# pir-tara.net
KiCad netlist of a schematic drawn in Altium Designer
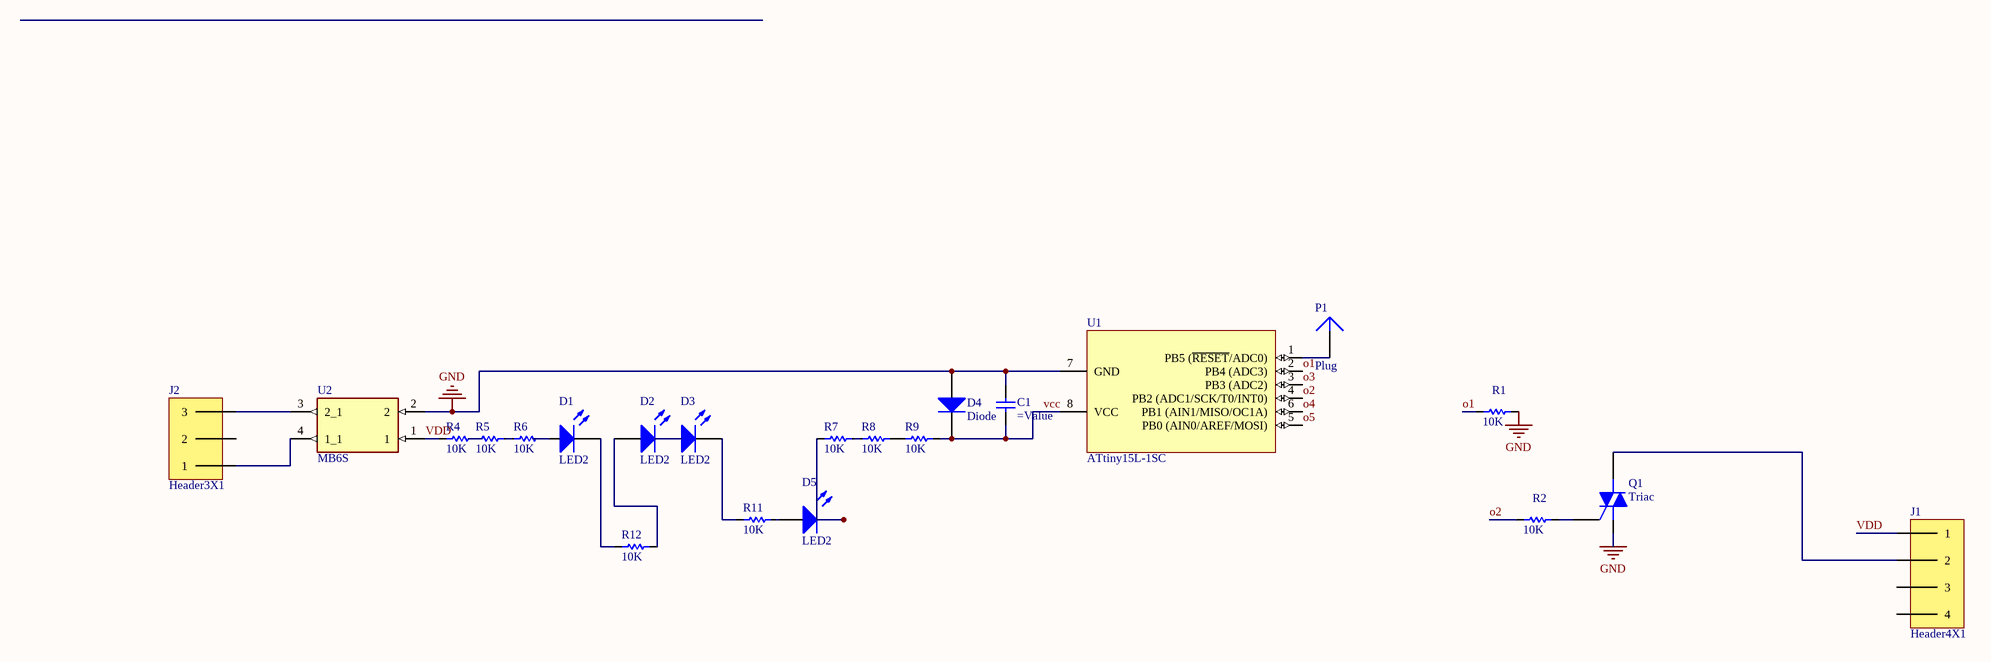
[diagram p0: pir-tara.SchDoc]

(export (version "E")
  (design (tool "Eeschema 10.0.6"))
  (components
    (comp (ref "C1")
      (value "~")
      (footprint "CAP 1206")
      (description "Capacitor")
      (libsource (lib "AltiumLib1") (part "Capacitor"))
    )
    (comp (ref "D1")
      (value "LED2")
      (footprint "3.2X1.6X1.1")
      (description "Typical RED, GREEN, YELLOW, AMBER GaAs LED")
      (fields (field (name "PUBLISHER") "Altium Limited"))
      (libsource (lib "Miscellaneous Devices") (part "LED2"))
    )
    (comp (ref "D2")
      (value "LED2")
      (footprint "3.2X1.6X1.1")
      (description "Typical RED, GREEN, YELLOW, AMBER GaAs LED")
      (fields (field (name "PUBLISHER") "Altium Limited"))
      (libsource (lib "Miscellaneous Devices") (part "LED2"))
    )
    (comp (ref "D3")
      (value "LED2")
      (footprint "3.2X1.6X1.1")
      (description "Typical RED, GREEN, YELLOW, AMBER GaAs LED")
      (fields (field (name "PUBLISHER") "Altium Limited"))
      (libsource (lib "Miscellaneous Devices") (part "LED2"))
    )
    (comp (ref "D4")
      (value "Diode")
      (footprint "C1206")
      (description "Default Diode")
      (fields (field (name "PUBLISHER") "Altium Limited"))
      (libsource (lib "Miscellaneous Devices") (part "Diode"))
    )
    (comp (ref "D5")
      (value "LED2")
      (footprint "3.2X1.6X1.1")
      (description "Typical RED, GREEN, YELLOW, AMBER GaAs LED")
      (fields (field (name "PUBLISHER") "Altium Limited"))
      (libsource (lib "Miscellaneous Devices") (part "LED2"))
    )
    (comp (ref "J1")
      (value "Header4X1")
      (footprint "HEADER 4X1")
      (libsource (lib "AltiumLib1") (part "Header4X1"))
    )
    (comp (ref "J2")
      (value "Header3X1")
      (footprint "HEADER 3X1")
      (libsource (lib "AltiumLib1") (part "Header3X1"))
    )
    (comp (ref "P1")
      (value "Plug")
      (footprint "PIN1")
      (fields (field (name "PUBLISHER") "Altium Limited"))
      (libsource (lib "Miscellaneous Connectors") (part "Plug"))
    )
    (comp (ref "Q1")
      (value "Triac")
      (footprint "SOT89N")
      (description "Silicon Bidirectional Triode Thyristor")
      (fields (field (name "PUBLISHER") "Altium Limited"))
      (libsource (lib "Miscellaneous Devices") (part "Triac"))
    )
    (comp (ref "R1")
      (value "10K")
      (footprint "RES 1206 (3216X08L)")
      (description "Resistor")
      (fields (field (name "TOLERANCE") "5%") (field (name "POWER") "1/4 W"))
      (libsource (lib "AltiumLib1") (part "Resistor"))
    )
    (comp (ref "R2")
      (value "10K")
      (footprint "RES 1206 (3216X08L)")
      (description "Resistor")
      (fields (field (name "TOLERANCE") "5%") (field (name "POWER") "1/4 W"))
      (libsource (lib "AltiumLib1") (part "Resistor"))
    )
    (comp (ref "R4")
      (value "10K")
      (footprint "RES 2010 (5026X08L)")
      (description "Resistor")
      (fields (field (name "TOLERANCE") "5%") (field (name "POWER") "1/4 W"))
      (libsource (lib "AltiumLib1") (part "Resistor"))
    )
    (comp (ref "R5")
      (value "10K")
      (footprint "RES 2010 (5026X08L)")
      (description "Resistor")
      (fields (field (name "TOLERANCE") "5%") (field (name "POWER") "1/4 W"))
      (libsource (lib "AltiumLib1") (part "Resistor"))
    )
    (comp (ref "R6")
      (value "10K")
      (footprint "RES 2010 (5026X08L)")
      (description "Resistor")
      (fields (field (name "TOLERANCE") "5%") (field (name "POWER") "1/4 W"))
      (libsource (lib "AltiumLib1") (part "Resistor"))
    )
    (comp (ref "R7")
      (value "10K")
      (footprint "RES 2010 (5026X08L)")
      (description "Resistor")
      (fields (field (name "TOLERANCE") "5%") (field (name "POWER") "1/4 W"))
      (libsource (lib "AltiumLib1") (part "Resistor"))
    )
    (comp (ref "R8")
      (value "10K")
      (footprint "RES 2010 (5026X08L)")
      (description "Resistor")
      (fields (field (name "TOLERANCE") "5%") (field (name "POWER") "1/4 W"))
      (libsource (lib "AltiumLib1") (part "Resistor"))
    )
    (comp (ref "R9")
      (value "10K")
      (footprint "RES 2010 (5026X08L)")
      (description "Resistor")
      (fields (field (name "TOLERANCE") "5%") (field (name "POWER") "1/4 W"))
      (libsource (lib "AltiumLib1") (part "Resistor"))
    )
    (comp (ref "R11")
      (value "10K")
      (footprint "RES 2010 (5026X08L)")
      (description "Resistor")
      (fields (field (name "TOLERANCE") "5%") (field (name "POWER") "1/4 W"))
      (libsource (lib "AltiumLib1") (part "Resistor"))
    )
    (comp (ref "R12")
      (value "10K")
      (footprint "RES 2010 (5026X08L)")
      (description "Resistor")
      (fields (field (name "TOLERANCE") "5%") (field (name "POWER") "1/4 W"))
      (libsource (lib "AltiumLib1") (part "Resistor"))
    )
    (comp (ref "U1")
      (value "ATtiny15L-1SC")
      (footprint "8S2_N")
      (description "8-Bit AVR Microcontroller with 1K Byte of Flash Memory")
      (fields (field (name "PUBLISHER") "Altium Limited"))
      (libsource (lib "Atmel Microcontroller 8-Bit AVR") (part "ATtiny15L-1SC"))
    )
    (comp (ref "U2")
      (value "MB6S")
      (footprint "SOIC245P670X270-4N")
      (description "Bridge Rectifier Single Phase Standard 600V Surface Mount 4-SOIC")
      (fields (field (name "MF") "ON Semiconductor") (field (name "DIGI-KEY_PART_NUMBER") "MB6SCT-ND"))
      (libsource (lib "MB6S") (part "MB6S"))
    )
  )
  (nets
    (net (code "1") (name "/VDD") (class "Default")
      (node (ref "J1") (pin "1") (pinfunction "1_1") (pintype "passive"))
      (node (ref "R4") (pin "1") (pinfunction "1_1") (pintype "passive"))
      (node (ref "U2") (pin "1") (pinfunction "1_1") (pintype "input"))
    )
    (net (code "2") (name "/o1") (class "Default")
      (node (ref "R1") (pin "1") (pinfunction "1_1") (pintype "passive"))
      (node (ref "U1") (pin "2") (pinfunction "PB4_(ADC3)_2") (pintype "bidirectional"))
    )
    (net (code "3") (name "/o2") (class "Default")
      (node (ref "R2") (pin "1") (pinfunction "1_1") (pintype "passive"))
      (node (ref "U1") (pin "4") (pinfunction "PB2_(ADC1/SCK/T0/INT0)_4") (pintype "bidirectional"))
    )
    (net (code "4") (name "/o3") (class "Default")
      (node (ref "U1") (pin "3") (pinfunction "PB3_(ADC2)_3") (pintype "bidirectional"))
    )
    (net (code "5") (name "/o4") (class "Default")
      (node (ref "U1") (pin "6") (pinfunction "PB1_(AIN1/MISO/OC1A)_6") (pintype "bidirectional"))
    )
    (net (code "6") (name "/o5") (class "Default")
      (node (ref "U1") (pin "5") (pinfunction "PB0_(AIN0/AREF/MOSI)_5") (pintype "bidirectional"))
    )
    (net (code "7") (name "/vcc") (class "Default")
      (node (ref "C1") (pin "1") (pinfunction "+_1") (pintype "passive"))
      (node (ref "D4") (pin "2") (pinfunction "K_2") (pintype "passive"))
      (node (ref "R9") (pin "2") (pinfunction "2_2") (pintype "passive"))
      (node (ref "U1") (pin "8") (pinfunction "VCC_8") (pintype "power_in"))
    )
    (net (code "8") (name "GND") (class "Default")
      (node (ref "C1") (pin "2") (pinfunction "-_2") (pintype "passive"))
      (node (ref "D4") (pin "1") (pinfunction "A_1") (pintype "passive"))
      (node (ref "Q1") (pin "1") (pinfunction "M1_1") (pintype "passive"))
      (node (ref "R1") (pin "2") (pinfunction "2_2") (pintype "passive"))
      (node (ref "U1") (pin "7") (pinfunction "GND_7") (pintype "power_in"))
      (node (ref "U2") (pin "2") (pinfunction "2_2") (pintype "input"))
    )
    (net (code "9") (name "Net-(D1-A)") (class "Default")
      (node (ref "D1") (pin "1") (pinfunction "A_1") (pintype "passive"))
      (node (ref "R6") (pin "2") (pinfunction "2_2") (pintype "passive"))
    )
    (net (code "10") (name "Net-(D1-K)") (class "Default")
      (node (ref "D1") (pin "2") (pinfunction "K_2") (pintype "passive"))
      (node (ref "R12") (pin "1") (pinfunction "1_1") (pintype "passive"))
    )
    (net (code "11") (name "Net-(D2-A)") (class "Default")
      (node (ref "D2") (pin "1") (pinfunction "A_1") (pintype "passive"))
      (node (ref "R12") (pin "2") (pinfunction "2_2") (pintype "passive"))
    )
    (net (code "12") (name "Net-(D2-K)") (class "Default")
      (node (ref "D2") (pin "2") (pinfunction "K_2") (pintype "passive"))
      (node (ref "D3") (pin "1") (pinfunction "A_1") (pintype "passive"))
    )
    (net (code "13") (name "Net-(D3-K)") (class "Default")
      (node (ref "D3") (pin "2") (pinfunction "K_2") (pintype "passive"))
      (node (ref "R11") (pin "1") (pinfunction "1_1") (pintype "passive"))
    )
    (net (code "14") (name "Net-(D5-A)") (class "Default")
      (node (ref "D5") (pin "1") (pinfunction "A_1") (pintype "passive"))
      (node (ref "R11") (pin "2") (pinfunction "2_2") (pintype "passive"))
    )
    (net (code "15") (name "Net-(D5-K)") (class "Default")
      (node (ref "D5") (pin "2") (pinfunction "K_2") (pintype "passive"))
      (node (ref "R7") (pin "1") (pinfunction "1_1") (pintype "passive"))
    )
    (net (code "16") (name "Net-(Q1-G)") (class "Default")
      (node (ref "Q1") (pin "3") (pinfunction "G_3") (pintype "passive"))
      (node (ref "R2") (pin "2") (pinfunction "2_2") (pintype "passive"))
    )
    (net (code "17") (name "Net-(Q1-M2)") (class "Default")
      (node (ref "J1") (pin "2") (pinfunction "2_2") (pintype "passive"))
      (node (ref "Q1") (pin "2") (pinfunction "M2_2") (pintype "passive"))
    )
    (net (code "18") (name "Net-(R4-Pad2)") (class "Default")
      (node (ref "R4") (pin "2") (pinfunction "2_2") (pintype "passive"))
      (node (ref "R5") (pin "1") (pinfunction "1_1") (pintype "passive"))
    )
    (net (code "19") (name "Net-(R5-Pad2)") (class "Default")
      (node (ref "R5") (pin "2") (pinfunction "2_2") (pintype "passive"))
      (node (ref "R6") (pin "1") (pinfunction "1_1") (pintype "passive"))
    )
    (net (code "20") (name "Net-(R7-Pad2)") (class "Default")
      (node (ref "R7") (pin "2") (pinfunction "2_2") (pintype "passive"))
      (node (ref "R8") (pin "1") (pinfunction "1_1") (pintype "passive"))
    )
    (net (code "21") (name "Net-(R8-Pad2)") (class "Default")
      (node (ref "R8") (pin "2") (pinfunction "2_2") (pintype "passive"))
      (node (ref "R9") (pin "1") (pinfunction "1_1") (pintype "passive"))
    )
    (net (code "22") (name "Net-(U1-PB5_(~{RESET}{slash}ADC0))") (class "Default")
      (node (ref "P1") (pin "1") (pinfunction "1_1") (pintype "passive"))
      (node (ref "U1") (pin "1") (pinfunction "PB5_(~{RESET}/ADC0)_1") (pintype "bidirectional"))
    )
    (net (code "23") (name "Net-(U2-1_1)") (class "Default")
      (node (ref "J2") (pin "1") (pinfunction "1_1") (pintype "passive"))
      (node (ref "U2") (pin "4") (pinfunction "1_1_4") (pintype "output"))
    )
    (net (code "24") (name "Net-(U2-2_1)") (class "Default")
      (node (ref "J2") (pin "3") (pinfunction "3_3") (pintype "passive"))
      (node (ref "U2") (pin "3") (pinfunction "2_1_3") (pintype "output"))
    )
    (net (code "25") (name "unconnected-(J1-Pad3)") (class "Default")
      (node (ref "J1") (pin "3") (pinfunction "3_3") (pintype "passive"))
    )
    (net (code "26") (name "unconnected-(J1-Pad4)") (class "Default")
      (node (ref "J1") (pin "4") (pinfunction "4_4") (pintype "passive"))
    )
    (net (code "27") (name "unconnected-(J2-Pad2)") (class "Default")
      (node (ref "J2") (pin "2") (pinfunction "2_2") (pintype "passive"))
    )
  )
)
